# RFDuino_badge.net
KiCad netlist of a schematic drawn in EAGLE
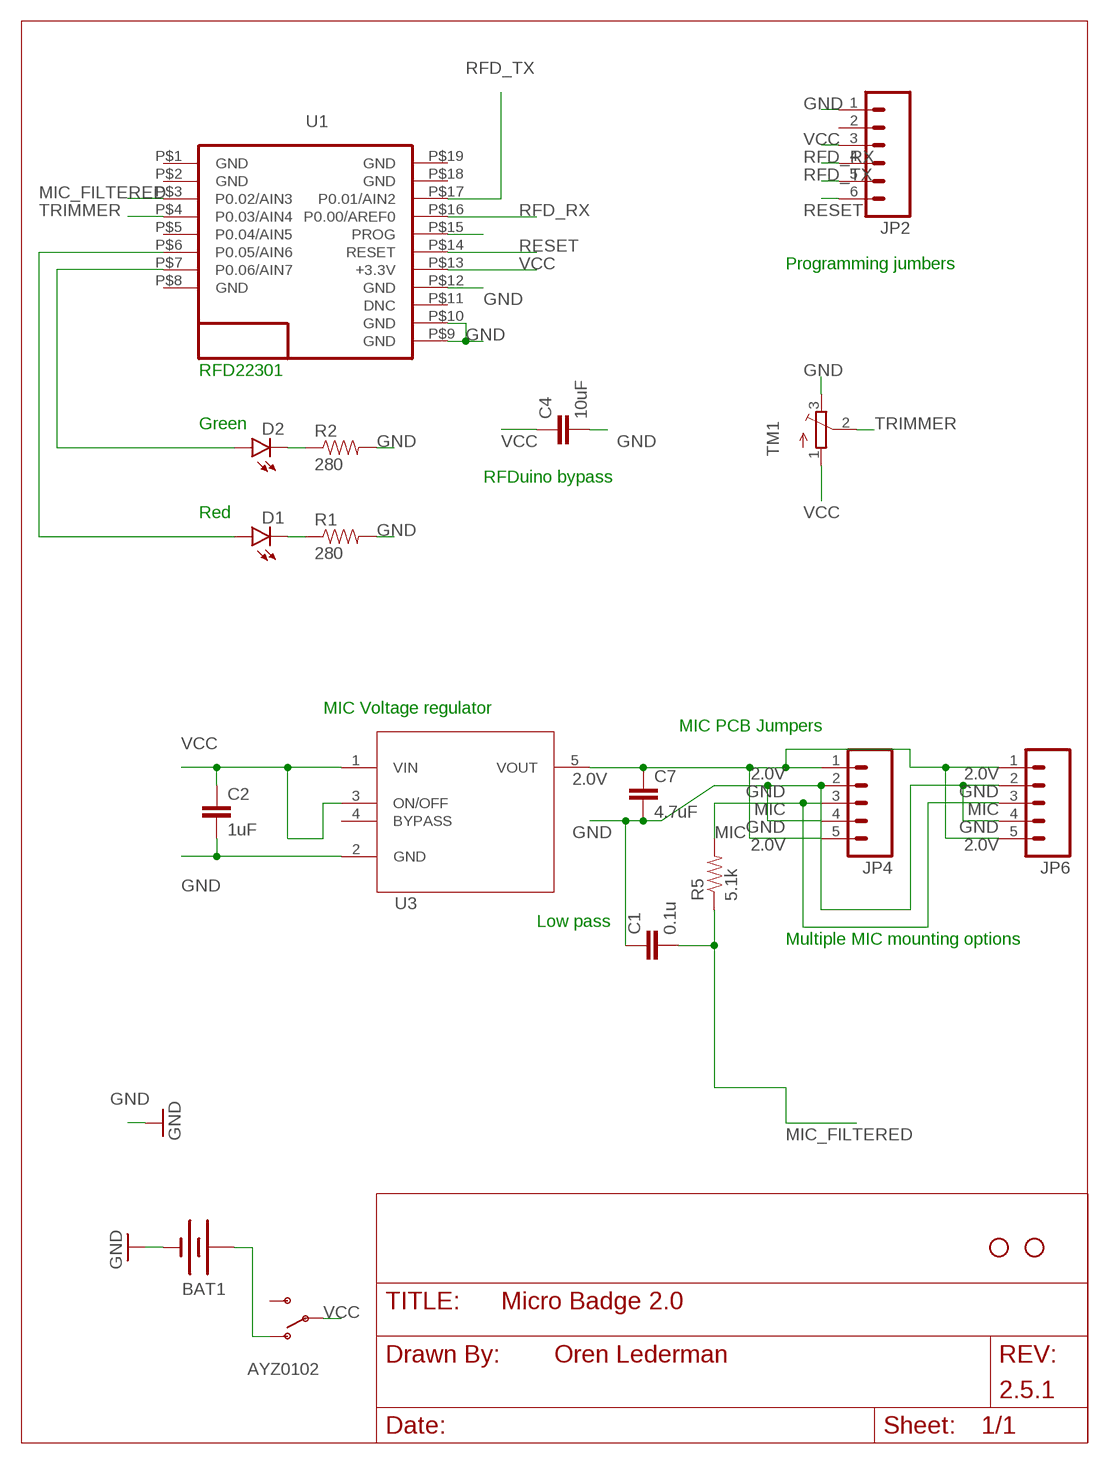
[diagram p0: schematic, sheet 1]

(export (version "E")
  (design (tool "Eeschema 10.0.6"))
  (components
    (comp (ref "AYZ0102")
      (value "AYZ0102AGRLCAYZ0102AGRLC")
      (footprint "eagle-import:KPS-1290")
      (libsource (lib "eagle-import") (part "AYZ0102AGRLCAYZ0102AGRLC"))
    )
    (comp (ref "BAT1")
      (value "BATTERY20MM_4LEGS_OVERPASTE")
      (footprint "eagle-import:BATTCON_20MM_4LEGS_OVERPASTE")
      (libsource (lib "eagle-import") (part "BATTERY20MM_4LEGS_OVERPASTE"))
    )
    (comp (ref "C1")
      (value "0.1u")
      (footprint "eagle-import:1206")
      (libsource (lib "eagle-import") (part "CAP1206"))
    )
    (comp (ref "C2")
      (value "1uF")
      (footprint "eagle-import:1206")
      (libsource (lib "eagle-import") (part "CAP1206"))
    )
    (comp (ref "C4")
      (value "10uF")
      (footprint "eagle-import:1206")
      (libsource (lib "eagle-import") (part "CAP1206"))
    )
    (comp (ref "C7")
      (value "4.7uF")
      (footprint "eagle-import:1206")
      (libsource (lib "eagle-import") (part "CAP1206"))
    )
    (comp (ref "D1")
      (value "LED1206")
      (footprint "eagle-import:LED-1206")
      (libsource (lib "eagle-import") (part "LED1206"))
    )
    (comp (ref "D2")
      (value "LED1206")
      (footprint "eagle-import:LED-1206")
      (libsource (lib "eagle-import") (part "LED1206"))
    )
    (comp (ref "JP2")
      (value "M06LONGPADS")
      (footprint "eagle-import:1X06_LONGPADS")
      (libsource (lib "eagle-import") (part "M06LONGPADS"))
    )
    (comp (ref "JP4")
      (value "M05PTH_LONGPADS")
      (footprint "eagle-import:1X05_LONGPADS")
      (libsource (lib "eagle-import") (part "M05PTH_LONGPADS"))
    )
    (comp (ref "JP6")
      (value "M05PTH")
      (footprint "eagle-import:1X05")
      (libsource (lib "eagle-import") (part "M05PTH"))
    )
    (comp (ref "R1")
      (value "280")
      (footprint "eagle-import:1206")
      (libsource (lib "eagle-import") (part "RESISTOR1206"))
    )
    (comp (ref "R2")
      (value "280")
      (footprint "eagle-import:1206")
      (libsource (lib "eagle-import") (part "RESISTOR1206"))
    )
    (comp (ref "R5")
      (value "5.1k")
      (footprint "eagle-import:1206")
      (libsource (lib "eagle-import") (part "RESISTOR1206"))
    )
    (comp (ref "STANDOFF1")
      (value "STAND-OFF")
      (footprint "eagle-import:STAND-OFF")
      (libsource (lib "eagle-import") (part "STAND-OFF"))
    )
    (comp (ref "STANDOFF2")
      (value "STAND-OFF")
      (footprint "eagle-import:STAND-OFF")
      (libsource (lib "eagle-import") (part "STAND-OFF"))
    )
    (comp (ref "TM1")
      (value "TRIMPOTTC33X")
      (footprint "eagle-import:TC33X")
      (libsource (lib "eagle-import") (part "TRIMPOTTC33X"))
    )
    (comp (ref "U1")
      (value "RFD22301")
      (footprint "eagle-import:RFD21733")
      (libsource (lib "eagle-import") (part "RFD22301"))
    )
    (comp (ref "U3")
      (value "LP2985AIM5-2.5")
      (footprint "eagle-import:SOT95P285X120-5N")
      (libsource (lib "eagle-import") (part "LP2985AIM5-2.5"))
    )
  )
  (nets
    (net (code "1") (name "/2.0V") (class "Default")
      (node (ref "C7") (pin "1") (pinfunction "1_1") (pintype "passive"))
      (node (ref "JP4") (pin "1") (pinfunction "1_1") (pintype "passive"))
      (node (ref "JP4") (pin "5") (pinfunction "5_5") (pintype "passive"))
      (node (ref "JP6") (pin "1") (pinfunction "1_1") (pintype "passive"))
      (node (ref "JP6") (pin "5") (pinfunction "5_5") (pintype "passive"))
      (node (ref "U3") (pin "5") (pinfunction "VOUT_5") (pintype "output"))
    )
    (net (code "2") (name "/MIC") (class "Default")
      (node (ref "JP4") (pin "3") (pinfunction "3_3") (pintype "passive"))
      (node (ref "JP6") (pin "3") (pinfunction "3_3") (pintype "passive"))
      (node (ref "R5") (pin "2") (pinfunction "2_2") (pintype "passive"))
    )
    (net (code "3") (name "/MIC_FILTERED") (class "Default")
      (node (ref "C1") (pin "2") (pinfunction "2_2") (pintype "passive"))
      (node (ref "R5") (pin "1") (pinfunction "1_1") (pintype "passive"))
      (node (ref "U1") (pin "P$3") (pinfunction "P0.02/AIN3_P$3") (pintype "bidirectional"))
    )
    (net (code "4") (name "/RESET") (class "Default")
      (node (ref "JP2") (pin "6") (pinfunction "6_6") (pintype "passive"))
      (node (ref "U1") (pin "P$14") (pinfunction "RESET_P$14") (pintype "bidirectional"))
    )
    (net (code "5") (name "/RFD_RX") (class "Default")
      (node (ref "JP2") (pin "4") (pinfunction "4_4") (pintype "passive"))
      (node (ref "U1") (pin "P$16") (pinfunction "P0.00/AREF0_P$16") (pintype "bidirectional"))
    )
    (net (code "6") (name "/RFD_TX") (class "Default")
      (node (ref "JP2") (pin "5") (pinfunction "5_5") (pintype "passive"))
      (node (ref "U1") (pin "P$17") (pinfunction "P0.01/AIN2_P$17") (pintype "bidirectional"))
    )
    (net (code "7") (name "/TRIMMER") (class "Default")
      (node (ref "TM1") (pin "2") (pinfunction "S_2") (pintype "passive"))
      (node (ref "U1") (pin "P$4") (pinfunction "P0.03/AIN4_P$4") (pintype "bidirectional"))
    )
    (net (code "8") (name "/VCC") (class "Default")
      (node (ref "AYZ0102") (pin "P") (pinfunction "P_P") (pintype "passive"))
      (node (ref "C2") (pin "1") (pinfunction "1_1") (pintype "passive"))
      (node (ref "C4") (pin "1") (pinfunction "1_1") (pintype "passive"))
      (node (ref "JP2") (pin "3") (pinfunction "3_3") (pintype "passive"))
      (node (ref "TM1") (pin "1") (pinfunction "A_1") (pintype "passive"))
      (node (ref "U1") (pin "P$13") (pinfunction "+3.3V_P$13") (pintype "bidirectional"))
      (node (ref "U3") (pin "1") (pinfunction "VIN_1") (pintype "power_in"))
      (node (ref "U3") (pin "3") (pinfunction "ON/OFF_3") (pintype "input"))
    )
    (net (code "9") (name "GND") (class "Default")
      (node (ref "BAT1") (pin "2") (pinfunction "-_2") (pintype "power_in"))
      (node (ref "C1") (pin "1") (pinfunction "1_1") (pintype "passive"))
      (node (ref "C2") (pin "2") (pinfunction "2_2") (pintype "passive"))
      (node (ref "C4") (pin "2") (pinfunction "2_2") (pintype "passive"))
      (node (ref "C7") (pin "2") (pinfunction "2_2") (pintype "passive"))
      (node (ref "JP2") (pin "1") (pinfunction "1_1") (pintype "passive"))
      (node (ref "JP4") (pin "2") (pinfunction "2_2") (pintype "passive"))
      (node (ref "JP4") (pin "4") (pinfunction "4_4") (pintype "passive"))
      (node (ref "JP6") (pin "2") (pinfunction "2_2") (pintype "passive"))
      (node (ref "JP6") (pin "4") (pinfunction "4_4") (pintype "passive"))
      (node (ref "R1") (pin "2") (pinfunction "2_2") (pintype "passive"))
      (node (ref "R2") (pin "2") (pinfunction "2_2") (pintype "passive"))
      (node (ref "TM1") (pin "3") (pinfunction "E_3") (pintype "passive"))
      (node (ref "U1") (pin "P$10") (pinfunction "GND_P$10") (pintype "bidirectional"))
      (node (ref "U1") (pin "P$12") (pinfunction "GND_P$12") (pintype "bidirectional"))
      (node (ref "U1") (pin "P$9") (pinfunction "GND_P$9") (pintype "bidirectional"))
      (node (ref "U3") (pin "2") (pinfunction "GND_2") (pintype "passive"))
    )
    (net (code "10") (name "Net-(BAT1-+)") (class "Default")
      (node (ref "AYZ0102") (pin "O") (pinfunction "O_O") (pintype "passive"))
      (node (ref "BAT1") (pin "1") (pinfunction "+_1") (pintype "power_in"))
    )
    (net (code "11") (name "Net-(D1-PadC)") (class "Default")
      (node (ref "D1") (pin "C") (pinfunction "C_C") (pintype "passive"))
      (node (ref "R1") (pin "1") (pinfunction "1_1") (pintype "passive"))
    )
    (net (code "12") (name "Net-(D2-PadC)") (class "Default")
      (node (ref "D2") (pin "C") (pinfunction "C_C") (pintype "passive"))
      (node (ref "R2") (pin "1") (pinfunction "1_1") (pintype "passive"))
    )
    (net (code "13") (name "Net-(U1-P0.05{slash}AIN6)") (class "Default")
      (node (ref "D1") (pin "A") (pinfunction "A_A") (pintype "passive"))
      (node (ref "U1") (pin "P$6") (pinfunction "P0.05/AIN6_P$6") (pintype "bidirectional"))
    )
    (net (code "14") (name "Net-(U1-P0.06{slash}AIN7)") (class "Default")
      (node (ref "D2") (pin "A") (pinfunction "A_A") (pintype "passive"))
      (node (ref "U1") (pin "P$7") (pinfunction "P0.06/AIN7_P$7") (pintype "bidirectional"))
    )
    (net (code "15") (name "unconnected-(AYZ0102-PadS)") (class "Default")
      (node (ref "AYZ0102") (pin "S") (pinfunction "S_S") (pintype "passive"))
    )
    (net (code "16") (name "unconnected-(JP2-Pad2)") (class "Default")
      (node (ref "JP2") (pin "2") (pinfunction "2_2") (pintype "passive"))
    )
    (net (code "17") (name "unconnected-(U1-DNC-PadP$11)") (class "Default")
      (node (ref "U1") (pin "P$11") (pinfunction "DNC_P$11") (pintype "bidirectional"))
    )
    (net (code "18") (name "unconnected-(U1-GND-PadP$1)") (class "Default")
      (node (ref "U1") (pin "P$1") (pinfunction "GND_P$1") (pintype "bidirectional"))
    )
    (net (code "19") (name "unconnected-(U1-GND-PadP$2)") (class "Default")
      (node (ref "U1") (pin "P$2") (pinfunction "GND_P$2") (pintype "bidirectional"))
    )
    (net (code "20") (name "unconnected-(U1-GND-PadP$8)") (class "Default")
      (node (ref "U1") (pin "P$8") (pinfunction "GND_P$8") (pintype "bidirectional"))
    )
    (net (code "21") (name "unconnected-(U1-GND-PadP$18)") (class "Default")
      (node (ref "U1") (pin "P$18") (pinfunction "GND_P$18") (pintype "bidirectional"))
    )
    (net (code "22") (name "unconnected-(U1-GND-PadP$19)") (class "Default")
      (node (ref "U1") (pin "P$19") (pinfunction "GND_P$19") (pintype "bidirectional"))
    )
    (net (code "23") (name "unconnected-(U1-P0.04{slash}AIN5-PadP$5)") (class "Default")
      (node (ref "U1") (pin "P$5") (pinfunction "P0.04/AIN5_P$5") (pintype "bidirectional"))
    )
    (net (code "24") (name "unconnected-(U1-PROG-PadP$15)") (class "Default")
      (node (ref "U1") (pin "P$15") (pinfunction "PROG_P$15") (pintype "bidirectional"))
    )
    (net (code "25") (name "unconnected-(U3-BYPASS-Pad4)") (class "Default")
      (node (ref "U3") (pin "4") (pinfunction "BYPASS_4") (pintype "passive"))
    )
  )
)
